# battery_monitor_6803-2_Rev4-uno_shield.net
KiCad netlist of a schematic drawn in EAGLE
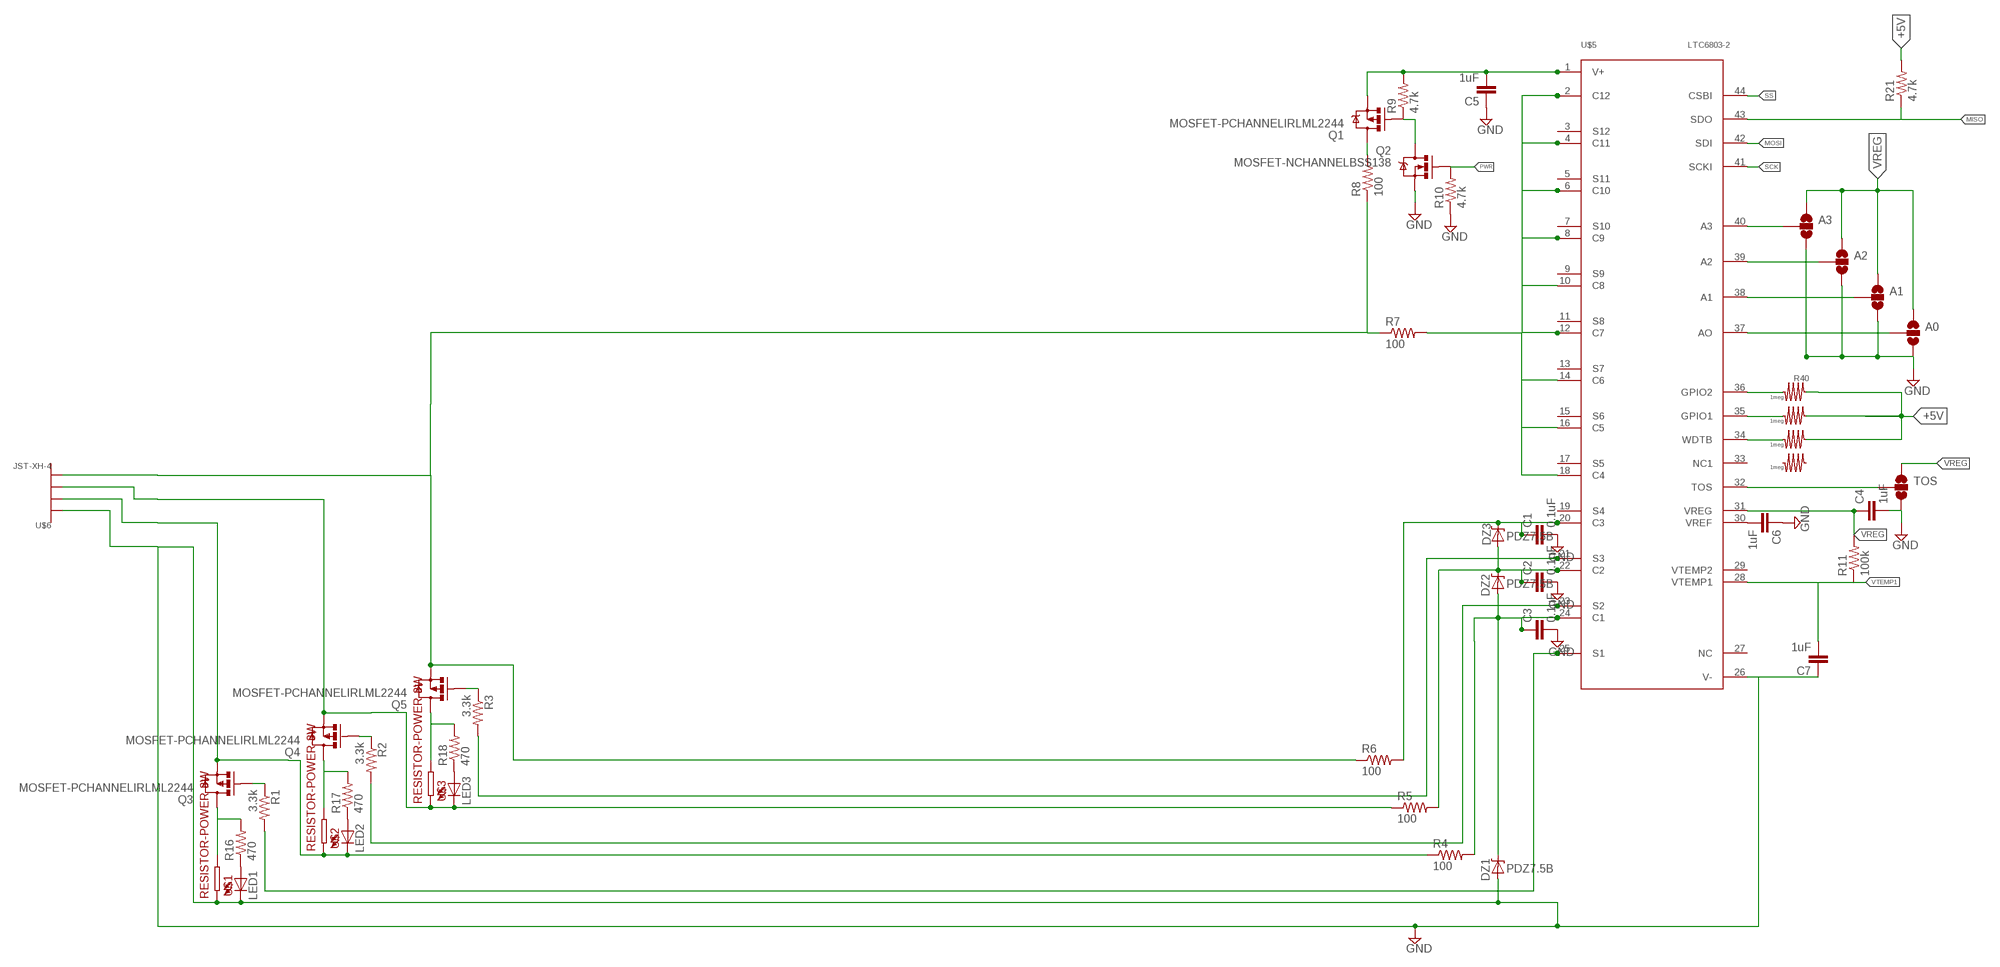
[diagram p0: schematic, sheet 1, part 1 of 2]
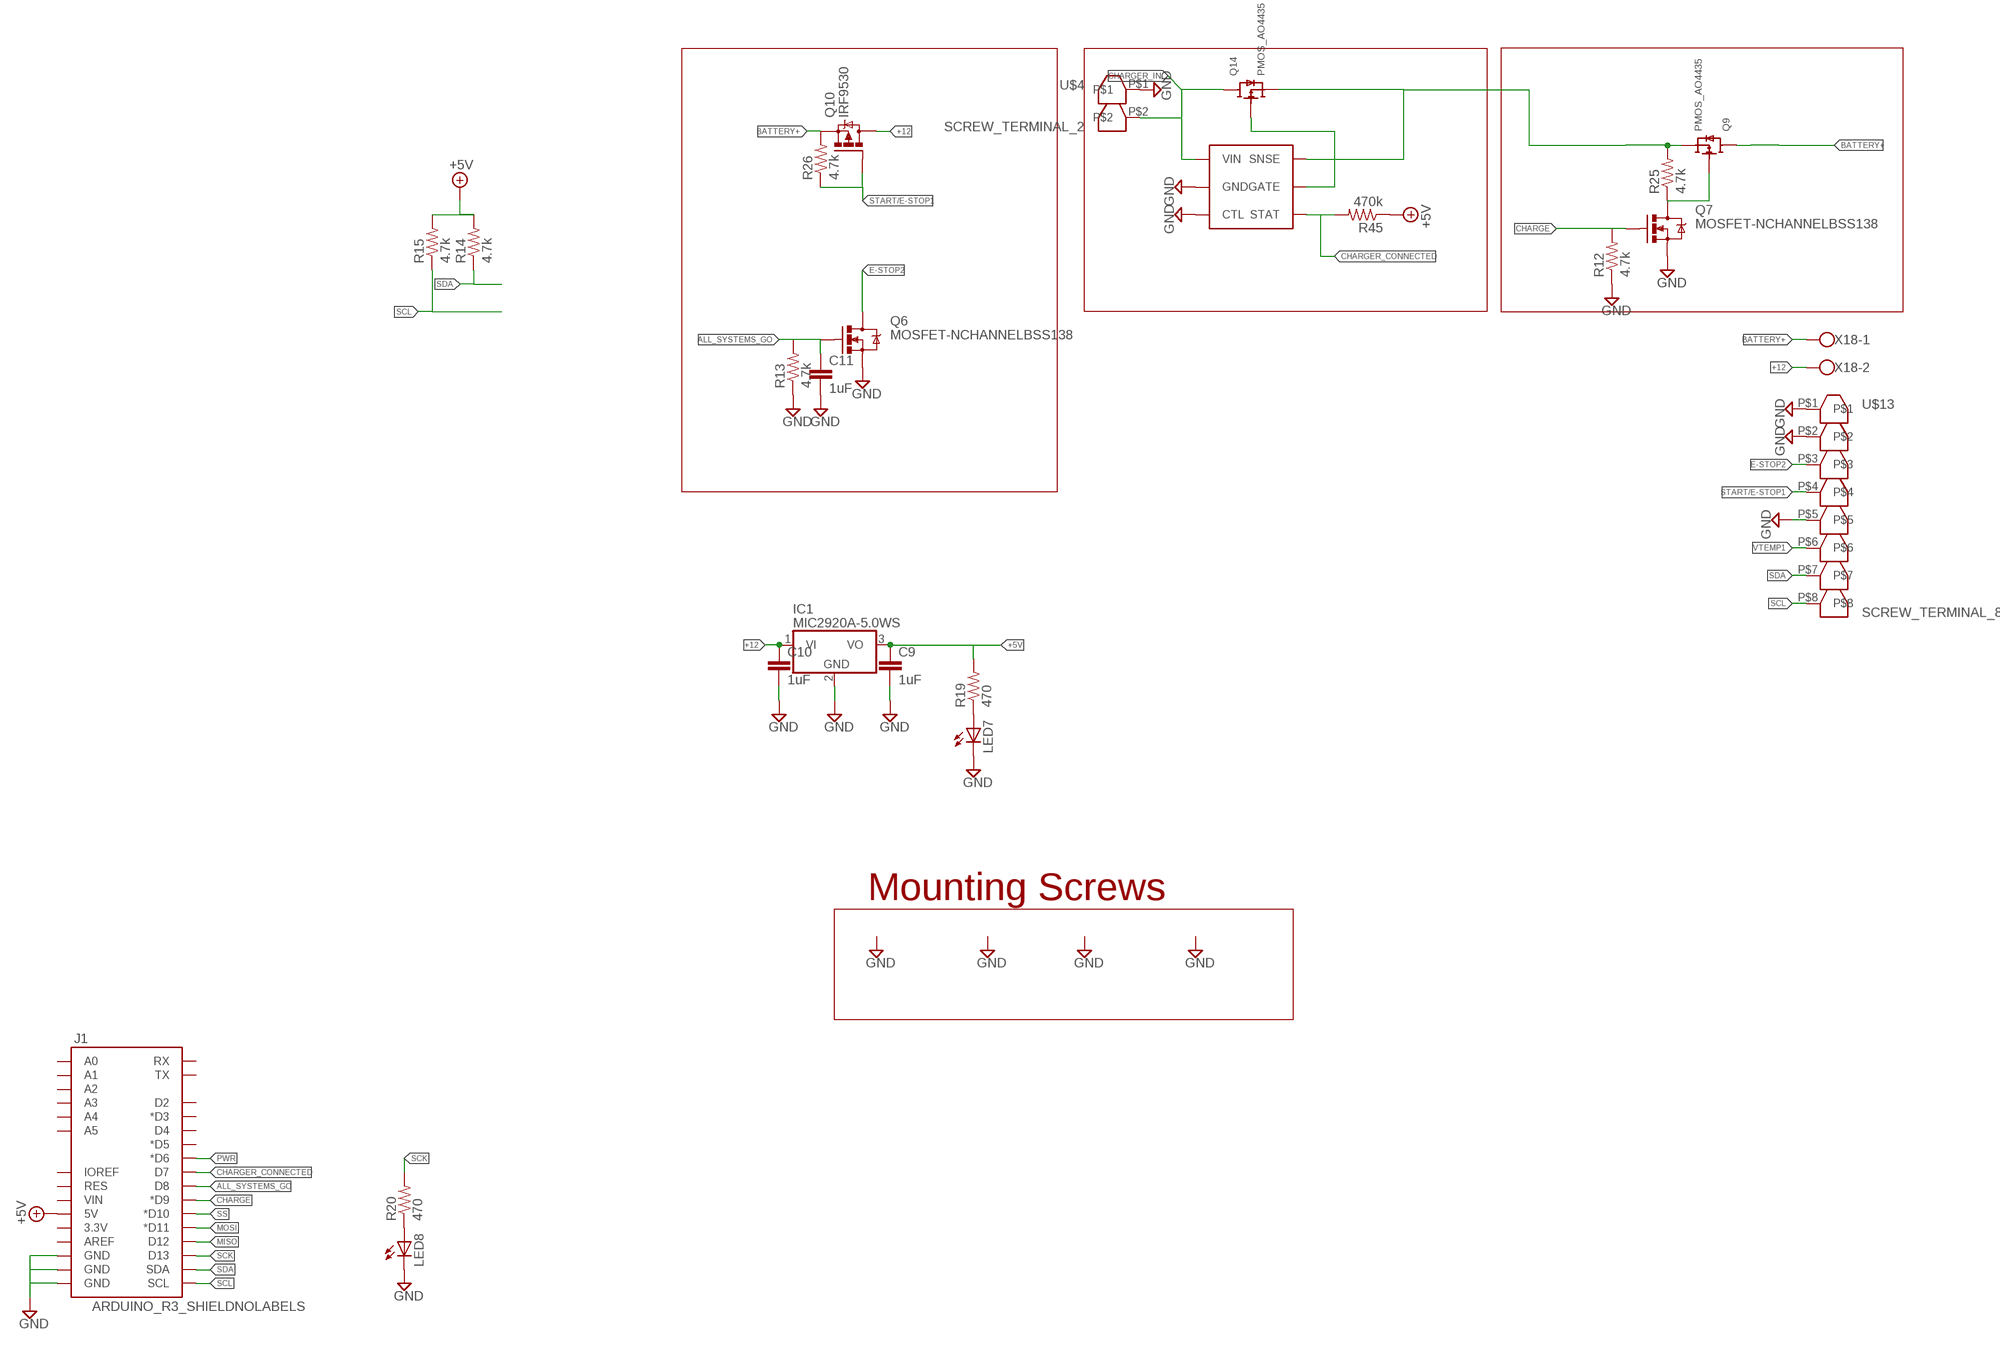
[diagram p1: schematic, sheet 1, part 2 of 2]

(export (version "E")
  (design (tool "Eeschema 10.0.6"))
  (components
    (comp (ref "A0")
      (value "SOLDERJUMPER_2WAYS")
      (footprint "eagle-import:SJ_3")
      (libsource (lib "eagle-import") (part "SOLDERJUMPER_2WAYS"))
    )
    (comp (ref "A1")
      (value "SOLDERJUMPER_2WAYS")
      (footprint "eagle-import:SJ_3")
      (libsource (lib "eagle-import") (part "SOLDERJUMPER_2WAYS"))
    )
    (comp (ref "A2")
      (value "SOLDERJUMPER_2WAYS")
      (footprint "eagle-import:SJ_3")
      (libsource (lib "eagle-import") (part "SOLDERJUMPER_2WAYS"))
    )
    (comp (ref "A3")
      (value "SOLDERJUMPER_2WAYS")
      (footprint "eagle-import:SJ_3")
      (libsource (lib "eagle-import") (part "SOLDERJUMPER_2WAYS"))
    )
    (comp (ref "C1")
      (value "0.1uF")
      (footprint "eagle-import:0603-CAP")
      (libsource (lib "eagle-import") (part "0.1UF-100V-10%(0603)"))
    )
    (comp (ref "C2")
      (value "0.1uF")
      (footprint "eagle-import:0603-CAP")
      (libsource (lib "eagle-import") (part "0.1UF-100V-10%(0603)"))
    )
    (comp (ref "C3")
      (value "0.1uF")
      (footprint "eagle-import:0603-CAP")
      (libsource (lib "eagle-import") (part "0.1UF-100V-10%(0603)"))
    )
    (comp (ref "C4")
      (value "1uF")
      (footprint "eagle-import:0603-CAP")
      (fields (field (name "PROD_ID") "CAP-08390"))
      (libsource (lib "eagle-import") (part "0.1UF-100V-10%(0603)"))
    )
    (comp (ref "C5")
      (value "1uF")
      (footprint "eagle-import:0603-CAP")
      (fields (field (name "PROD_ID") "CAP-08390"))
      (libsource (lib "eagle-import") (part "0.1UF-100V-10%(0603)"))
    )
    (comp (ref "C6")
      (value "1uF")
      (footprint "eagle-import:0603-CAP")
      (fields (field (name "PROD_ID") "CAP-08390"))
      (libsource (lib "eagle-import") (part "0.1UF-100V-10%(0603)"))
    )
    (comp (ref "C7")
      (value "1uF")
      (footprint "eagle-import:0603-CAP")
      (fields (field (name "PROD_ID") "CAP-08390"))
      (libsource (lib "eagle-import") (part "0.1UF-100V-10%(0603)"))
    )
    (comp (ref "C9")
      (value "1uF")
      (footprint "eagle-import:0603-CAP")
      (fields (field (name "PROD_ID") "CAP-08390"))
      (libsource (lib "eagle-import") (part "0.1UF-100V-10%(0603)"))
    )
    (comp (ref "C10")
      (value "1uF")
      (footprint "eagle-import:0603-CAP")
      (fields (field (name "PROD_ID") "CAP-08390"))
      (libsource (lib "eagle-import") (part "0.1UF-100V-10%(0603)"))
    )
    (comp (ref "C11")
      (value "1uF")
      (footprint "eagle-import:0603-CAP")
      (fields (field (name "PROD_ID") "CAP-08390"))
      (libsource (lib "eagle-import") (part "0.1UF-100V-10%(0603)"))
    )
    (comp (ref "DZ1")
      (value "PDZ7.5B")
      (footprint "eagle-import:SOD-323")
      (libsource (lib "eagle-import") (part "DIODE-ZENER-BZT52"))
    )
    (comp (ref "DZ2")
      (value "PDZ7.5B")
      (footprint "eagle-import:SOD-323")
      (libsource (lib "eagle-import") (part "DIODE-ZENER-BZT52"))
    )
    (comp (ref "DZ3")
      (value "PDZ7.5B")
      (footprint "eagle-import:SOD-323")
      (libsource (lib "eagle-import") (part "DIODE-ZENER-BZT52"))
    )
    (comp (ref "IC1")
      (value "MIC2920A-5.0WS")
      (footprint "eagle-import:SOT223")
      (libsource (lib "eagle-import") (part "MCP1703DB"))
    )
    (comp (ref "J1")
      (value "ARDUINO_R3_SHIELDNOLABELS")
      (footprint "eagle-import:UNO_R3_SHIELD_NOLABELS")
      (libsource (lib "eagle-import") (part "ARDUINO_R3_SHIELDNOLABELS"))
    )
    (comp (ref "LED1")
      (value "LED0603")
      (footprint "eagle-import:LED-0603")
      (libsource (lib "eagle-import") (part "LED0603"))
    )
    (comp (ref "LED2")
      (value "LED0603")
      (footprint "eagle-import:LED-0603")
      (libsource (lib "eagle-import") (part "LED0603"))
    )
    (comp (ref "LED3")
      (value "LED0603")
      (footprint "eagle-import:LED-0603")
      (libsource (lib "eagle-import") (part "LED0603"))
    )
    (comp (ref "LED7")
      (value "LED0603")
      (footprint "eagle-import:LED-0603")
      (libsource (lib "eagle-import") (part "LED0603"))
    )
    (comp (ref "LED8")
      (value "LED0603")
      (footprint "eagle-import:LED-0603")
      (libsource (lib "eagle-import") (part "LED0603"))
    )
    (comp (ref "Q1")
      (value "MOSFET-PCHANNELIRLML2244")
      (footprint "eagle-import:SOT23-3")
      (libsource (lib "eagle-import") (part "MOSFET-PCHANNELIRLML2244"))
    )
    (comp (ref "Q2")
      (value "MOSFET-NCHANNELBSS138")
      (footprint "eagle-import:SOT23")
      (libsource (lib "eagle-import") (part "MOSFET-NCHANNELBSS138"))
    )
    (comp (ref "Q3")
      (value "MOSFET-PCHANNELIRLML2244")
      (footprint "eagle-import:SOT23-3")
      (libsource (lib "eagle-import") (part "MOSFET-PCHANNELIRLML2244"))
    )
    (comp (ref "Q4")
      (value "MOSFET-PCHANNELIRLML2244")
      (footprint "eagle-import:SOT23-3")
      (libsource (lib "eagle-import") (part "MOSFET-PCHANNELIRLML2244"))
    )
    (comp (ref "Q5")
      (value "MOSFET-PCHANNELIRLML2244")
      (footprint "eagle-import:SOT23-3")
      (libsource (lib "eagle-import") (part "MOSFET-PCHANNELIRLML2244"))
    )
    (comp (ref "Q6")
      (value "MOSFET-NCHANNELBSS138")
      (footprint "eagle-import:SOT23")
      (libsource (lib "eagle-import") (part "MOSFET-NCHANNELBSS138"))
    )
    (comp (ref "Q7")
      (value "MOSFET-NCHANNELBSS138")
      (footprint "eagle-import:SOT23")
      (libsource (lib "eagle-import") (part "MOSFET-NCHANNELBSS138"))
    )
    (comp (ref "Q9")
      (value "PMOS_AO4435")
      (footprint "eagle-import:SOIC8")
      (libsource (lib "eagle-import") (part "PMOS_AO4435"))
    )
    (comp (ref "Q10")
      (value "IRF9530")
      (footprint "eagle-import:TO220BV")
      (libsource (lib "eagle-import") (part "IRF9530"))
    )
    (comp (ref "Q14")
      (value "PMOS_AO4435")
      (footprint "eagle-import:SOIC8")
      (libsource (lib "eagle-import") (part "PMOS_AO4435"))
    )
    (comp (ref "R1")
      (value "3.3k")
      (footprint "eagle-import:0603-RES")
      (libsource (lib "eagle-import") (part "3.3KOHM1/10W1%(0603)"))
    )
    (comp (ref "R2")
      (value "3.3k")
      (footprint "eagle-import:0603-RES")
      (libsource (lib "eagle-import") (part "3.3KOHM1/10W1%(0603)"))
    )
    (comp (ref "R3")
      (value "3.3k")
      (footprint "eagle-import:0603-RES")
      (libsource (lib "eagle-import") (part "3.3KOHM1/10W1%(0603)"))
    )
    (comp (ref "R4")
      (value "100")
      (footprint "eagle-import:0603-RES")
      (libsource (lib "eagle-import") (part "3.3KOHM1/10W1%(0603)"))
    )
    (comp (ref "R5")
      (value "100")
      (footprint "eagle-import:0603-RES")
      (libsource (lib "eagle-import") (part "3.3KOHM1/10W1%(0603)"))
    )
    (comp (ref "R6")
      (value "100")
      (footprint "eagle-import:0603-RES")
      (libsource (lib "eagle-import") (part "3.3KOHM1/10W1%(0603)"))
    )
    (comp (ref "R7")
      (value "100")
      (footprint "eagle-import:0603-RES")
      (libsource (lib "eagle-import") (part "3.3KOHM1/10W1%(0603)"))
    )
    (comp (ref "R8")
      (value "100")
      (footprint "eagle-import:0603-RES")
      (libsource (lib "eagle-import") (part "3.3KOHM1/10W1%(0603)"))
    )
    (comp (ref "R9")
      (value "4.7k")
      (footprint "eagle-import:0603-RES")
      (libsource (lib "eagle-import") (part "3.3KOHM1/10W1%(0603)"))
    )
    (comp (ref "R10")
      (value "4.7k")
      (footprint "eagle-import:0603-RES")
      (libsource (lib "eagle-import") (part "3.3KOHM1/10W1%(0603)"))
    )
    (comp (ref "R11")
      (value "100k")
      (footprint "eagle-import:0603-RES")
      (libsource (lib "eagle-import") (part "3.3KOHM1/10W1%(0603)"))
    )
    (comp (ref "R12")
      (value "4.7k")
      (footprint "eagle-import:0603-RES")
      (libsource (lib "eagle-import") (part "3.3KOHM1/10W1%(0603)"))
    )
    (comp (ref "R13")
      (value "4.7k")
      (footprint "eagle-import:0603-RES")
      (libsource (lib "eagle-import") (part "3.3KOHM1/10W1%(0603)"))
    )
    (comp (ref "R14")
      (value "4.7k")
      (footprint "eagle-import:0603-RES")
      (libsource (lib "eagle-import") (part "3.3KOHM1/10W1%(0603)"))
    )
    (comp (ref "R15")
      (value "4.7k")
      (footprint "eagle-import:0603-RES")
      (libsource (lib "eagle-import") (part "3.3KOHM1/10W1%(0603)"))
    )
    (comp (ref "R16")
      (value "470")
      (footprint "eagle-import:0603-RES")
      (fields (field (name "PROD_ID") "RES-07851"))
      (libsource (lib "eagle-import") (part "3.3KOHM1/10W1%(0603)"))
    )
    (comp (ref "R17")
      (value "470")
      (footprint "eagle-import:0603-RES")
      (fields (field (name "PROD_ID") "RES-07851"))
      (libsource (lib "eagle-import") (part "3.3KOHM1/10W1%(0603)"))
    )
    (comp (ref "R18")
      (value "470")
      (footprint "eagle-import:0603-RES")
      (fields (field (name "PROD_ID") "RES-07851"))
      (libsource (lib "eagle-import") (part "3.3KOHM1/10W1%(0603)"))
    )
    (comp (ref "R19")
      (value "470")
      (footprint "eagle-import:0603-RES")
      (fields (field (name "PROD_ID") "RES-07851"))
      (libsource (lib "eagle-import") (part "3.3KOHM1/10W1%(0603)"))
    )
    (comp (ref "R20")
      (value "470")
      (footprint "eagle-import:0603-RES")
      (fields (field (name "PROD_ID") "RES-07851"))
      (libsource (lib "eagle-import") (part "3.3KOHM1/10W1%(0603)"))
    )
    (comp (ref "R21")
      (value "4.7k")
      (footprint "eagle-import:0603-RES")
      (fields (field (name "PROD_ID") "RES-07851"))
      (libsource (lib "eagle-import") (part "3.3KOHM1/10W1%(0603)"))
    )
    (comp (ref "R25")
      (value "4.7k")
      (footprint "eagle-import:0603-RES")
      (fields (field (name "PROD_ID") "RES-07851"))
      (libsource (lib "eagle-import") (part "3.3KOHM1/10W1%(0603)"))
    )
    (comp (ref "R26")
      (value "4.7k")
      (footprint "eagle-import:0603-RES")
      (fields (field (name "PROD_ID") "RES-07851"))
      (libsource (lib "eagle-import") (part "3.3KOHM1/10W1%(0603)"))
    )
    (comp (ref "R40")
      (value "1meg")
      (footprint "eagle-import:RESISTOR-ARRAY-0603")
      (libsource (lib "eagle-import") (part "RESISTOR-742C083"))
    )
    (comp (ref "R45")
      (value "470k")
      (footprint "eagle-import:0603-RES")
      (fields (field (name "PROD_ID") "RES-07851"))
      (libsource (lib "eagle-import") (part "3.3KOHM1/10W1%(0603)"))
    )
    (comp (ref "TOS")
      (value "SOLDERJUMPER_2WAYS")
      (footprint "eagle-import:SJ_3")
      (libsource (lib "eagle-import") (part "SOLDERJUMPER_2WAYS"))
    )
    (comp (ref "U$1")
      (value "RESISTOR-POWER-3W")
      (footprint "eagle-import:RESISTOR-3W")
      (libsource (lib "eagle-import") (part "RESISTOR-POWER-3W"))
    )
    (comp (ref "U$2")
      (value "RESISTOR-POWER-3W")
      (footprint "eagle-import:RESISTOR-3W")
      (libsource (lib "eagle-import") (part "RESISTOR-POWER-3W"))
    )
    (comp (ref "U$3")
      (value "RESISTOR-POWER-3W")
      (footprint "eagle-import:RESISTOR-3W")
      (libsource (lib "eagle-import") (part "RESISTOR-POWER-3W"))
    )
    (comp (ref "U$4")
      (value "SCREW_TERMINAL_2")
      (footprint "eagle-import:SCREW_TERMINAL_2")
      (libsource (lib "eagle-import") (part "SCREW_TERMINAL_2"))
    )
    (comp (ref "U$5")
      (value "LTC6803-2")
      (footprint "eagle-import:FSOP-44")
      (libsource (lib "eagle-import") (part "LTC6803-2"))
    )
    (comp (ref "U$6")
      (value "JST-XH-4")
      (footprint "eagle-import:JST-XH-4")
      (libsource (lib "eagle-import") (part "JST-XH-4"))
    )
    (comp (ref "U$12")
      (value "LTC4412")
      (footprint "eagle-import:SOT-23-6")
      (libsource (lib "eagle-import") (part "LTC4412"))
    )
    (comp (ref "U$13")
      (value "SCREW_TERMINAL_8")
      (footprint "eagle-import:SCREW_TERMINAL_8")
      (libsource (lib "eagle-import") (part "SCREW_TERMINAL_8"))
    )
    (comp (ref "X18")
      (value "W237-102")
      (footprint "eagle-import:W237-102")
      (fields (field (name "MPN") "237-102"))
      (libsource (lib "eagle-import") (part "W237-102"))
    )
  )
  (nets
    (net (code "1") (name "+5V") (class "Default")
      (node (ref "C9") (pin "1") (pinfunction "1_1") (pintype "passive"))
      (node (ref "IC1") (pin "3") (pinfunction "VO_3") (pintype "passive"))
      (node (ref "J1") (pin "5V") (pinfunction "5V_5V") (pintype "bidirectional"))
      (node (ref "R14") (pin "2") (pinfunction "2_2") (pintype "passive"))
      (node (ref "R15") (pin "2") (pinfunction "2_2") (pintype "passive"))
      (node (ref "R19") (pin "2") (pinfunction "2_2") (pintype "passive"))
      (node (ref "R21") (pin "2") (pinfunction "2_2") (pintype "passive"))
      (node (ref "R40") (pin "P$1") (pinfunction "P$1_P$1") (pintype "bidirectional"))
      (node (ref "R40") (pin "P$3") (pinfunction "P$3_P$3") (pintype "bidirectional"))
      (node (ref "R40") (pin "P$5") (pinfunction "P$5_P$5") (pintype "bidirectional"))
      (node (ref "R45") (pin "1") (pinfunction "1_1") (pintype "passive"))
    )
    (net (code "2") (name "+12") (class "Default")
      (node (ref "C10") (pin "1") (pinfunction "1_1") (pintype "passive"))
      (node (ref "IC1") (pin "1") (pinfunction "VI_1") (pintype "input"))
      (node (ref "Q10") (pin "D") (pinfunction "D_D") (pintype "passive"))
      (node (ref "X18") (pin "2") (pinfunction "KL_2") (pintype "passive"))
    )
    (net (code "3") (name "ALL_SYSTEMS_GO") (class "Default")
      (node (ref "C11") (pin "1") (pinfunction "1_1") (pintype "passive"))
      (node (ref "J1") (pin "D8") (pinfunction "D8_D8") (pintype "bidirectional"))
      (node (ref "Q6") (pin "1") (pinfunction "G_1") (pintype "passive"))
      (node (ref "R13") (pin "2") (pinfunction "2_2") (pintype "passive"))
    )
    (net (code "4") (name "BATTERY+") (class "Default")
      (node (ref "Q10") (pin "S") (pinfunction "S_S") (pintype "passive"))
      (node (ref "Q9") (pin "5") (pinfunction "DRAIN_5") (pintype "bidirectional"))
      (node (ref "Q9") (pin "6") (pinfunction "DRAIN_6") (pintype "bidirectional"))
      (node (ref "Q9") (pin "7") (pinfunction "DRAIN_7") (pintype "bidirectional"))
      (node (ref "Q9") (pin "8") (pinfunction "DRAIN_8") (pintype "bidirectional"))
      (node (ref "R26") (pin "2") (pinfunction "2_2") (pintype "passive"))
      (node (ref "X18") (pin "1") (pinfunction "KL_1") (pintype "passive"))
    )
    (net (code "5") (name "CHARGE") (class "Default")
      (node (ref "J1") (pin "D9") (pinfunction "*D9_D9") (pintype "bidirectional"))
      (node (ref "Q7") (pin "1") (pinfunction "G_1") (pintype "passive"))
      (node (ref "R12") (pin "2") (pinfunction "2_2") (pintype "passive"))
    )
    (net (code "6") (name "CHARGER_CONNECTED") (class "Default")
      (node (ref "J1") (pin "D7") (pinfunction "D7_D7") (pintype "bidirectional"))
      (node (ref "R45") (pin "2") (pinfunction "2_2") (pintype "passive"))
      (node (ref "U$12") (pin "P$4") (pinfunction "STAT_P$4") (pintype "bidirectional"))
    )
    (net (code "7") (name "CHARGER_IN") (class "Default")
      (node (ref "Q14") (pin "5") (pinfunction "DRAIN_5") (pintype "bidirectional"))
      (node (ref "Q14") (pin "6") (pinfunction "DRAIN_6") (pintype "bidirectional"))
      (node (ref "Q14") (pin "7") (pinfunction "DRAIN_7") (pintype "bidirectional"))
      (node (ref "Q14") (pin "8") (pinfunction "DRAIN_8") (pintype "bidirectional"))
      (node (ref "U$12") (pin "P$1") (pinfunction "VIN_P$1") (pintype "bidirectional"))
      (node (ref "U$4") (pin "P$2") (pinfunction "P$2_P$2") (pintype "bidirectional"))
    )
    (net (code "8") (name "E-STOP2") (class "Default")
      (node (ref "Q6") (pin "3") (pinfunction "D_3") (pintype "passive"))
      (node (ref "U$13") (pin "P$3") (pinfunction "P$3_P$3") (pintype "bidirectional"))
    )
    (net (code "9") (name "GND") (class "Default")
      (node (ref "A0") (pin "3") (pinfunction "3_3") (pintype "passive"))
      (node (ref "A1") (pin "3") (pinfunction "3_3") (pintype "passive"))
      (node (ref "A2") (pin "3") (pinfunction "3_3") (pintype "passive"))
      (node (ref "A3") (pin "3") (pinfunction "3_3") (pintype "passive"))
      (node (ref "C1") (pin "2") (pinfunction "2_2") (pintype "passive"))
      (node (ref "C10") (pin "2") (pinfunction "2_2") (pintype "passive"))
      (node (ref "C11") (pin "2") (pinfunction "2_2") (pintype "passive"))
      (node (ref "C2") (pin "2") (pinfunction "2_2") (pintype "passive"))
      (node (ref "C3") (pin "2") (pinfunction "2_2") (pintype "passive"))
      (node (ref "C4") (pin "2") (pinfunction "2_2") (pintype "passive"))
      (node (ref "C5") (pin "1") (pinfunction "1_1") (pintype "passive"))
      (node (ref "C6") (pin "1") (pinfunction "1_1") (pintype "passive"))
      (node (ref "C7") (pin "1") (pinfunction "1_1") (pintype "passive"))
      (node (ref "C9") (pin "2") (pinfunction "2_2") (pintype "passive"))
      (node (ref "DZ1") (pin "2") (pinfunction "A_2") (pintype "passive"))
      (node (ref "IC1") (pin "2") (pinfunction "GND_2") (pintype "passive"))
      (node (ref "J1") (pin "GND@0") (pinfunction "GND_GND@0") (pintype "bidirectional"))
      (node (ref "J1") (pin "GND@1") (pinfunction "GND_GND@1") (pintype "bidirectional"))
      (node (ref "J1") (pin "GND@2") (pinfunction "GND_GND@2") (pintype "bidirectional"))
      (node (ref "LED1") (pin "C") (pinfunction "C_C") (pintype "passive"))
      (node (ref "LED7") (pin "C") (pinfunction "C_C") (pintype "passive"))
      (node (ref "LED8") (pin "C") (pinfunction "C_C") (pintype "passive"))
      (node (ref "Q2") (pin "2") (pinfunction "S_2") (pintype "passive"))
      (node (ref "Q6") (pin "2") (pinfunction "S_2") (pintype "passive"))
      (node (ref "Q7") (pin "2") (pinfunction "S_2") (pintype "passive"))
      (node (ref "R10") (pin "1") (pinfunction "1_1") (pintype "passive"))
      (node (ref "R12") (pin "1") (pinfunction "1_1") (pintype "passive"))
      (node (ref "R13") (pin "1") (pinfunction "1_1") (pintype "passive"))
      (node (ref "TOS") (pin "3") (pinfunction "3_3") (pintype "passive"))
      (node (ref "U$1") (pin "P$2") (pinfunction "P$2_P$2") (pintype "bidirectional"))
      (node (ref "U$12") (pin "P$2") (pinfunction "GND_P$2") (pintype "bidirectional"))
      (node (ref "U$12") (pin "P$3") (pinfunction "CTL_P$3") (pintype "bidirectional"))
      (node (ref "U$13") (pin "P$1") (pinfunction "P$1_P$1") (pintype "bidirectional"))
      (node (ref "U$13") (pin "P$2") (pinfunction "P$2_P$2") (pintype "bidirectional"))
      (node (ref "U$13") (pin "P$5") (pinfunction "P$5_P$5") (pintype "bidirectional"))
      (node (ref "U$4") (pin "P$1") (pinfunction "P$1_P$1") (pintype "bidirectional"))
      (node (ref "U$5") (pin "26") (pinfunction "V-_26") (pintype "bidirectional"))
      (node (ref "U$6") (pin "P$4") (pinfunction "P$4_P$4") (pintype "bidirectional"))
    )
    (net (code "10") (name "MISO") (class "Default")
      (node (ref "J1") (pin "D12") (pinfunction "D12_D12") (pintype "bidirectional"))
      (node (ref "R21") (pin "1") (pinfunction "1_1") (pintype "passive"))
      (node (ref "U$5") (pin "43") (pinfunction "SDO_43") (pintype "bidirectional"))
    )
    (net (code "11") (name "MOSI") (class "Default")
      (node (ref "J1") (pin "D11") (pinfunction "*D11_D11") (pintype "bidirectional"))
      (node (ref "U$5") (pin "42") (pinfunction "SDI_42") (pintype "bidirectional"))
    )
    (net (code "12") (name "Net-(DZ1-C)") (class "Default")
      (node (ref "C3") (pin "1") (pinfunction "1_1") (pintype "passive"))
      (node (ref "DZ1") (pin "1") (pinfunction "C_1") (pintype "passive"))
      (node (ref "DZ2") (pin "2") (pinfunction "A_2") (pintype "passive"))
      (node (ref "R4") (pin "2") (pinfunction "2_2") (pintype "passive"))
      (node (ref "U$5") (pin "24") (pinfunction "C1_24") (pintype "bidirectional"))
    )
    (net (code "13") (name "Net-(DZ2-C)") (class "Default")
      (node (ref "C2") (pin "1") (pinfunction "1_1") (pintype "passive"))
      (node (ref "DZ2") (pin "1") (pinfunction "C_1") (pintype "passive"))
      (node (ref "DZ3") (pin "2") (pinfunction "A_2") (pintype "passive"))
      (node (ref "R5") (pin "2") (pinfunction "2_2") (pintype "passive"))
      (node (ref "U$5") (pin "22") (pinfunction "C2_22") (pintype "bidirectional"))
    )
    (net (code "14") (name "Net-(DZ3-C)") (class "Default")
      (node (ref "C1") (pin "1") (pinfunction "1_1") (pintype "passive"))
      (node (ref "DZ3") (pin "1") (pinfunction "C_1") (pintype "passive"))
      (node (ref "R6") (pin "2") (pinfunction "2_2") (pintype "passive"))
      (node (ref "U$5") (pin "20") (pinfunction "C3_20") (pintype "bidirectional"))
    )
    (net (code "15") (name "Net-(LED1-PadA)") (class "Default")
      (node (ref "LED1") (pin "A") (pinfunction "A_A") (pintype "passive"))
      (node (ref "R16") (pin "1") (pinfunction "1_1") (pintype "passive"))
    )
    (net (code "16") (name "Net-(LED2-PadA)") (class "Default")
      (node (ref "LED2") (pin "A") (pinfunction "A_A") (pintype "passive"))
      (node (ref "R17") (pin "1") (pinfunction "1_1") (pintype "passive"))
    )
    (net (code "17") (name "Net-(LED3-PadA)") (class "Default")
      (node (ref "LED3") (pin "A") (pinfunction "A_A") (pintype "passive"))
      (node (ref "R18") (pin "1") (pinfunction "1_1") (pintype "passive"))
    )
    (net (code "18") (name "Net-(LED7-PadA)") (class "Default")
      (node (ref "LED7") (pin "A") (pinfunction "A_A") (pintype "passive"))
      (node (ref "R19") (pin "1") (pinfunction "1_1") (pintype "passive"))
    )
    (net (code "19") (name "Net-(LED8-PadA)") (class "Default")
      (node (ref "LED8") (pin "A") (pinfunction "A_A") (pintype "passive"))
      (node (ref "R20") (pin "1") (pinfunction "1_1") (pintype "passive"))
    )
    (net (code "20") (name "Net-(Q1-D)") (class "Default")
      (node (ref "Q1") (pin "3") (pinfunction "D_3") (pintype "passive"))
      (node (ref "R8") (pin "2") (pinfunction "2_2") (pintype "passive"))
    )
    (net (code "21") (name "Net-(Q1-G)") (class "Default")
      (node (ref "Q1") (pin "1") (pinfunction "G_1") (pintype "passive"))
      (node (ref "Q2") (pin "3") (pinfunction "D_3") (pintype "passive"))
      (node (ref "R9") (pin "1") (pinfunction "1_1") (pintype "passive"))
    )
    (net (code "22") (name "Net-(Q1-S)") (class "Default")
      (node (ref "C5") (pin "2") (pinfunction "2_2") (pintype "passive"))
      (node (ref "Q1") (pin "2") (pinfunction "S_2") (pintype "passive"))
      (node (ref "R9") (pin "2") (pinfunction "2_2") (pintype "passive"))
      (node (ref "U$5") (pin "1") (pinfunction "V+_1") (pintype "bidirectional"))
    )
    (net (code "23") (name "Net-(Q3-D)") (class "Default")
      (node (ref "Q3") (pin "3") (pinfunction "D_3") (pintype "passive"))
      (node (ref "R16") (pin "2") (pinfunction "2_2") (pintype "passive"))
      (node (ref "U$1") (pin "P$1") (pinfunction "P$1_P$1") (pintype "bidirectional"))
    )
    (net (code "24") (name "Net-(Q3-G)") (class "Default")
      (node (ref "Q3") (pin "1") (pinfunction "G_1") (pintype "passive"))
      (node (ref "R1") (pin "1") (pinfunction "1_1") (pintype "passive"))
    )
    (net (code "25") (name "Net-(Q3-S)") (class "Default")
      (node (ref "LED2") (pin "C") (pinfunction "C_C") (pintype "passive"))
      (node (ref "Q3") (pin "2") (pinfunction "S_2") (pintype "passive"))
      (node (ref "R4") (pin "1") (pinfunction "1_1") (pintype "passive"))
      (node (ref "U$2") (pin "P$2") (pinfunction "P$2_P$2") (pintype "bidirectional"))
      (node (ref "U$6") (pin "P$3") (pinfunction "P$3_P$3") (pintype "bidirectional"))
    )
    (net (code "26") (name "Net-(Q4-D)") (class "Default")
      (node (ref "Q4") (pin "3") (pinfunction "D_3") (pintype "passive"))
      (node (ref "R17") (pin "2") (pinfunction "2_2") (pintype "passive"))
      (node (ref "U$2") (pin "P$1") (pinfunction "P$1_P$1") (pintype "bidirectional"))
    )
    (net (code "27") (name "Net-(Q4-G)") (class "Default")
      (node (ref "Q4") (pin "1") (pinfunction "G_1") (pintype "passive"))
      (node (ref "R2") (pin "1") (pinfunction "1_1") (pintype "passive"))
    )
    (net (code "28") (name "Net-(Q4-S)") (class "Default")
      (node (ref "LED3") (pin "C") (pinfunction "C_C") (pintype "passive"))
      (node (ref "Q4") (pin "2") (pinfunction "S_2") (pintype "passive"))
      (node (ref "R5") (pin "1") (pinfunction "1_1") (pintype "passive"))
      (node (ref "U$3") (pin "P$2") (pinfunction "P$2_P$2") (pintype "bidirectional"))
      (node (ref "U$6") (pin "P$2") (pinfunction "P$2_P$2") (pintype "bidirectional"))
    )
    (net (code "29") (name "Net-(Q5-D)") (class "Default")
      (node (ref "Q5") (pin "3") (pinfunction "D_3") (pintype "passive"))
      (node (ref "R18") (pin "2") (pinfunction "2_2") (pintype "passive"))
      (node (ref "U$3") (pin "P$1") (pinfunction "P$1_P$1") (pintype "bidirectional"))
    )
    (net (code "30") (name "Net-(Q5-G)") (class "Default")
      (node (ref "Q5") (pin "1") (pinfunction "G_1") (pintype "passive"))
      (node (ref "R3") (pin "1") (pinfunction "1_1") (pintype "passive"))
    )
    (net (code "31") (name "Net-(Q5-S)") (class "Default")
      (node (ref "Q5") (pin "2") (pinfunction "S_2") (pintype "passive"))
      (node (ref "R6") (pin "1") (pinfunction "1_1") (pintype "passive"))
      (node (ref "R7") (pin "1") (pinfunction "1_1") (pintype "passive"))
      (node (ref "R8") (pin "1") (pinfunction "1_1") (pintype "passive"))
      (node (ref "U$6") (pin "P$1") (pinfunction "P$1_P$1") (pintype "bidirectional"))
    )
    (net (code "32") (name "Net-(Q7-D)") (class "Default")
      (node (ref "Q7") (pin "3") (pinfunction "D_3") (pintype "passive"))
      (node (ref "Q9") (pin "4") (pinfunction "GATE_4") (pintype "bidirectional"))
      (node (ref "R25") (pin "1") (pinfunction "1_1") (pintype "passive"))
    )
    (net (code "33") (name "Net-(Q14-GATE)") (class "Default")
      (node (ref "Q14") (pin "4") (pinfunction "GATE_4") (pintype "bidirectional"))
      (node (ref "U$12") (pin "P$5") (pinfunction "GATE_P$5") (pintype "bidirectional"))
    )
    (net (code "34") (name "Net-(U$5-A1)") (class "Default")
      (node (ref "A1") (pin "2") (pinfunction "2_2") (pintype "passive"))
      (node (ref "U$5") (pin "38") (pinfunction "A1_38") (pintype "bidirectional"))
    )
    (net (code "35") (name "Net-(U$5-A2)") (class "Default")
      (node (ref "A2") (pin "2") (pinfunction "2_2") (pintype "passive"))
      (node (ref "U$5") (pin "39") (pinfunction "A2_39") (pintype "bidirectional"))
    )
    (net (code "36") (name "Net-(U$5-A3)") (class "Default")
      (node (ref "A3") (pin "2") (pinfunction "2_2") (pintype "passive"))
      (node (ref "U$5") (pin "40") (pinfunction "A3_40") (pintype "bidirectional"))
    )
    (net (code "37") (name "Net-(U$5-AO)") (class "Default")
      (node (ref "A0") (pin "2") (pinfunction "2_2") (pintype "passive"))
      (node (ref "U$5") (pin "37") (pinfunction "AO_37") (pintype "bidirectional"))
    )
    (net (code "38") (name "Net-(U$5-C10)") (class "Default")
      (node (ref "R7") (pin "2") (pinfunction "2_2") (pintype "passive"))
      (node (ref "U$5") (pin "10") (pinfunction "C8_10") (pintype "bidirectional"))
      (node (ref "U$5") (pin "12") (pinfunction "C7_12") (pintype "bidirectional"))
      (node (ref "U$5") (pin "14") (pinfunction "C6_14") (pintype "bidirectional"))
      (node (ref "U$5") (pin "16") (pinfunction "C5_16") (pintype "bidirectional"))
      (node (ref "U$5") (pin "18") (pinfunction "C4_18") (pintype "bidirectional"))
      (node (ref "U$5") (pin "2") (pinfunction "C12_2") (pintype "bidirectional"))
      (node (ref "U$5") (pin "4") (pinfunction "C11_4") (pintype "bidirectional"))
      (node (ref "U$5") (pin "6") (pinfunction "C10_6") (pintype "bidirectional"))
      (node (ref "U$5") (pin "8") (pinfunction "C9_8") (pintype "bidirectional"))
    )
    (net (code "39") (name "Net-(U$5-GPIO1)") (class "Default")
      (node (ref "R40") (pin "P$4") (pinfunction "P$4_P$4") (pintype "bidirectional"))
      (node (ref "U$5") (pin "35") (pinfunction "GPIO1_35") (pintype "bidirectional"))
    )
    (net (code "40") (name "Net-(U$5-GPIO2)") (class "Default")
      (node (ref "R40") (pin "P$2") (pinfunction "P$2_P$2") (pintype "bidirectional"))
      (node (ref "U$5") (pin "36") (pinfunction "GPIO2_36") (pintype "bidirectional"))
    )
    (net (code "41") (name "Net-(U$5-S1)") (class "Default")
      (node (ref "R1") (pin "2") (pinfunction "2_2") (pintype "passive"))
      (node (ref "U$5") (pin "25") (pinfunction "S1_25") (pintype "bidirectional"))
    )
    (net (code "42") (name "Net-(U$5-S2)") (class "Default")
      (node (ref "R2") (pin "2") (pinfunction "2_2") (pintype "passive"))
      (node (ref "U$5") (pin "23") (pinfunction "S2_23") (pintype "bidirectional"))
    )
    (net (code "43") (name "Net-(U$5-S3)") (class "Default")
      (node (ref "R3") (pin "2") (pinfunction "2_2") (pintype "passive"))
      (node (ref "U$5") (pin "21") (pinfunction "S3_21") (pintype "bidirectional"))
    )
    (net (code "44") (name "Net-(U$5-TOS)") (class "Default")
      (node (ref "TOS") (pin "2") (pinfunction "2_2") (pintype "passive"))
      (node (ref "U$5") (pin "32") (pinfunction "TOS_32") (pintype "bidirectional"))
    )
    (net (code "45") (name "Net-(U$5-VREF)") (class "Default")
      (node (ref "C6") (pin "2") (pinfunction "2_2") (pintype "passive"))
      (node (ref "U$5") (pin "30") (pinfunction "VREF_30") (pintype "bidirectional"))
    )
    (net (code "46") (name "Net-(U$5-WDTB)") (class "Default")
      (node (ref "R40") (pin "P$6") (pinfunction "P$6_P$6") (pintype "bidirectional"))
      (node (ref "U$5") (pin "34") (pinfunction "WDTB_34") (pintype "bidirectional"))
    )
    (net (code "47") (name "Net-(U$12-SNSE)") (class "Default")
      (node (ref "Q14") (pin "1") (pinfunction "SOURCE_1") (pintype "bidirectional"))
      (node (ref "Q14") (pin "2") (pinfunction "SOURCE_2") (pintype "bidirectional"))
      (node (ref "Q14") (pin "3") (pinfunction "SOURCE_3") (pintype "bidirectional"))
      (node (ref "Q9") (pin "1") (pinfunction "SOURCE_1") (pintype "bidirectional"))
      (node (ref "Q9") (pin "2") (pinfunction "SOURCE_2") (pintype "bidirectional"))
      (node (ref "Q9") (pin "3") (pinfunction "SOURCE_3") (pintype "bidirectional"))
      (node (ref "R25") (pin "2") (pinfunction "2_2") (pintype "passive"))
      (node (ref "U$12") (pin "P$6") (pinfunction "SNSE_P$6") (pintype "bidirectional"))
    )
    (net (code "48") (name "PWR") (class "Default")
      (node (ref "J1") (pin "D6") (pinfunction "*D6_D6") (pintype "bidirectional"))
      (node (ref "Q2") (pin "1") (pinfunction "G_1") (pintype "passive"))
      (node (ref "R10") (pin "2") (pinfunction "2_2") (pintype "passive"))
    )
    (net (code "49") (name "SCK") (class "Default")
      (node (ref "J1") (pin "D13") (pinfunction "D13_D13") (pintype "bidirectional"))
      (node (ref "R20") (pin "2") (pinfunction "2_2") (pintype "passive"))
      (node (ref "U$5") (pin "41") (pinfunction "SCKI_41") (pintype "bidirectional"))
    )
    (net (code "50") (name "SCL") (class "Default")
      (node (ref "J1") (pin "SCL") (pinfunction "SCL_SCL") (pintype "bidirectional"))
      (node (ref "R15") (pin "1") (pinfunction "1_1") (pintype "passive"))
      (node (ref "U$13") (pin "P$8") (pinfunction "P$8_P$8") (pintype "bidirectional"))
    )
    (net (code "51") (name "SDA") (class "Default")
      (node (ref "J1") (pin "SDA") (pinfunction "SDA_SDA") (pintype "bidirectional"))
      (node (ref "R14") (pin "1") (pinfunction "1_1") (pintype "passive"))
      (node (ref "U$13") (pin "P$7") (pinfunction "P$7_P$7") (pintype "bidirectional"))
    )
    (net (code "52") (name "SS") (class "Default")
      (node (ref "J1") (pin "D10") (pinfunction "*D10_D10") (pintype "bidirectional"))
      (node (ref "U$5") (pin "44") (pinfunction "CSBI_44") (pintype "bidirectional"))
    )
    (net (code "53") (name "START{slash}E-STOP1") (class "Default")
      (node (ref "Q10") (pin "G") (pinfunction "G_G") (pintype "passive"))
      (node (ref "R26") (pin "1") (pinfunction "1_1") (pintype "passive"))
      (node (ref "U$13") (pin "P$4") (pinfunction "P$4_P$4") (pintype "bidirectional"))
    )
    (net (code "54") (name "VREG") (class "Default")
      (node (ref "A0") (pin "1") (pinfunction "1_1") (pintype "passive"))
      (node (ref "A1") (pin "1") (pinfunction "1_1") (pintype "passive"))
      (node (ref "A2") (pin "1") (pinfunction "1_1") (pintype "passive"))
      (node (ref "A3") (pin "1") (pinfunction "1_1") (pintype "passive"))
      (node (ref "C4") (pin "1") (pinfunction "1_1") (pintype "passive"))
      (node (ref "R11") (pin "2") (pinfunction "2_2") (pintype "passive"))
      (node (ref "TOS") (pin "1") (pinfunction "1_1") (pintype "passive"))
      (node (ref "U$5") (pin "31") (pinfunction "VREG_31") (pintype "bidirectional"))
    )
    (net (code "55") (name "VTEMP1") (class "Default")
      (node (ref "C7") (pin "2") (pinfunction "2_2") (pintype "passive"))
      (node (ref "R11") (pin "1") (pinfunction "1_1") (pintype "passive"))
      (node (ref "U$13") (pin "P$6") (pinfunction "P$6_P$6") (pintype "bidirectional"))
      (node (ref "U$5") (pin "28") (pinfunction "VTEMP1_28") (pintype "bidirectional"))
    )
    (net (code "56") (name "unconnected-(J1-*D3-PadD3)") (class "Default")
      (node (ref "J1") (pin "D3") (pinfunction "*D3_D3") (pintype "bidirectional"))
    )
    (net (code "57") (name "unconnected-(J1-*D5-PadD5)") (class "Default")
      (node (ref "J1") (pin "D5") (pinfunction "*D5_D5") (pintype "bidirectional"))
    )
    (net (code "58") (name "unconnected-(J1-Pad3.3V)") (class "Default")
      (node (ref "J1") (pin "3.3V") (pinfunction "3.3V_3.3V") (pintype "bidirectional"))
    )
    (net (code "59") (name "unconnected-(J1-PadA0)") (class "Default")
      (node (ref "J1") (pin "A0") (pinfunction "A0_A0") (pintype "bidirectional"))
    )
    (net (code "60") (name "unconnected-(J1-PadA1)") (class "Default")
      (node (ref "J1") (pin "A1") (pinfunction "A1_A1") (pintype "bidirectional"))
    )
    (net (code "61") (name "unconnected-(J1-PadA2)") (class "Default")
      (node (ref "J1") (pin "A2") (pinfunction "A2_A2") (pintype "bidirectional"))
    )
    (net (code "62") (name "unconnected-(J1-PadA3)") (class "Default")
      (node (ref "J1") (pin "A3") (pinfunction "A3_A3") (pintype "bidirectional"))
    )
    (net (code "63") (name "unconnected-(J1-PadA4)") (class "Default")
      (node (ref "J1") (pin "A4") (pinfunction "A4_A4") (pintype "bidirectional"))
    )
    (net (code "64") (name "unconnected-(J1-PadA5)") (class "Default")
      (node (ref "J1") (pin "A5") (pinfunction "A5_A5") (pintype "bidirectional"))
    )
    (net (code "65") (name "unconnected-(J1-PadAREF)") (class "Default")
      (node (ref "J1") (pin "AREF") (pinfunction "AREF_AREF") (pintype "bidirectional"))
    )
    (net (code "66") (name "unconnected-(J1-PadD2)") (class "Default")
      (node (ref "J1") (pin "D2") (pinfunction "D2_D2") (pintype "bidirectional"))
    )
    (net (code "67") (name "unconnected-(J1-PadD4)") (class "Default")
      (node (ref "J1") (pin "D4") (pinfunction "D4_D4") (pintype "bidirectional"))
    )
    (net (code "68") (name "unconnected-(J1-PadIOREF)") (class "Default")
      (node (ref "J1") (pin "IOREF") (pinfunction "IOREF_IOREF") (pintype "bidirectional"))
    )
    (net (code "69") (name "unconnected-(J1-PadRES)") (class "Default")
      (node (ref "J1") (pin "RES") (pinfunction "RES_RES") (pintype "bidirectional"))
    )
    (net (code "70") (name "unconnected-(J1-PadRX)") (class "Default")
      (node (ref "J1") (pin "RX") (pinfunction "RX_RX") (pintype "bidirectional"))
    )
    (net (code "71") (name "unconnected-(J1-PadTX)") (class "Default")
      (node (ref "J1") (pin "TX") (pinfunction "TX_TX") (pintype "bidirectional"))
    )
    (net (code "72") (name "unconnected-(J1-PadVIN)") (class "Default")
      (node (ref "J1") (pin "VIN") (pinfunction "VIN_VIN") (pintype "bidirectional"))
    )
    (net (code "73") (name "unconnected-(R40-PadP$7)") (class "Default")
      (node (ref "R40") (pin "P$7") (pinfunction "P$7_P$7") (pintype "bidirectional"))
    )
    (net (code "74") (name "unconnected-(R40-PadP$8)") (class "Default")
      (node (ref "R40") (pin "P$8") (pinfunction "P$8_P$8") (pintype "bidirectional"))
    )
    (net (code "75") (name "unconnected-(U$5-NC-Pad27)") (class "Default")
      (node (ref "U$5") (pin "27") (pinfunction "NC_27") (pintype "bidirectional"))
    )
    (net (code "76") (name "unconnected-(U$5-NC1-Pad33)") (class "Default")
      (node (ref "U$5") (pin "33") (pinfunction "NC1_33") (pintype "bidirectional"))
    )
    (net (code "77") (name "unconnected-(U$5-S4-Pad19)") (class "Default")
      (node (ref "U$5") (pin "19") (pinfunction "S4_19") (pintype "bidirectional"))
    )
    (net (code "78") (name "unconnected-(U$5-S5-Pad17)") (class "Default")
      (node (ref "U$5") (pin "17") (pinfunction "S5_17") (pintype "bidirectional"))
    )
    (net (code "79") (name "unconnected-(U$5-S6-Pad15)") (class "Default")
      (node (ref "U$5") (pin "15") (pinfunction "S6_15") (pintype "bidirectional"))
    )
    (net (code "80") (name "unconnected-(U$5-S7-Pad13)") (class "Default")
      (node (ref "U$5") (pin "13") (pinfunction "S7_13") (pintype "bidirectional"))
    )
    (net (code "81") (name "unconnected-(U$5-S8-Pad11)") (class "Default")
      (node (ref "U$5") (pin "11") (pinfunction "S8_11") (pintype "bidirectional"))
    )
    (net (code "82") (name "unconnected-(U$5-S9-Pad9)") (class "Default")
      (node (ref "U$5") (pin "9") (pinfunction "S9_9") (pintype "bidirectional"))
    )
    (net (code "83") (name "unconnected-(U$5-S10-Pad7)") (class "Default")
      (node (ref "U$5") (pin "7") (pinfunction "S10_7") (pintype "bidirectional"))
    )
    (net (code "84") (name "unconnected-(U$5-S11-Pad5)") (class "Default")
      (node (ref "U$5") (pin "5") (pinfunction "S11_5") (pintype "bidirectional"))
    )
    (net (code "85") (name "unconnected-(U$5-S12-Pad3)") (class "Default")
      (node (ref "U$5") (pin "3") (pinfunction "S12_3") (pintype "bidirectional"))
    )
    (net (code "86") (name "unconnected-(U$5-VTEMP2-Pad29)") (class "Default")
      (node (ref "U$5") (pin "29") (pinfunction "VTEMP2_29") (pintype "bidirectional"))
    )
  )
)
